# Balance.net
KiCad netlist of a schematic drawn in Altium Designer
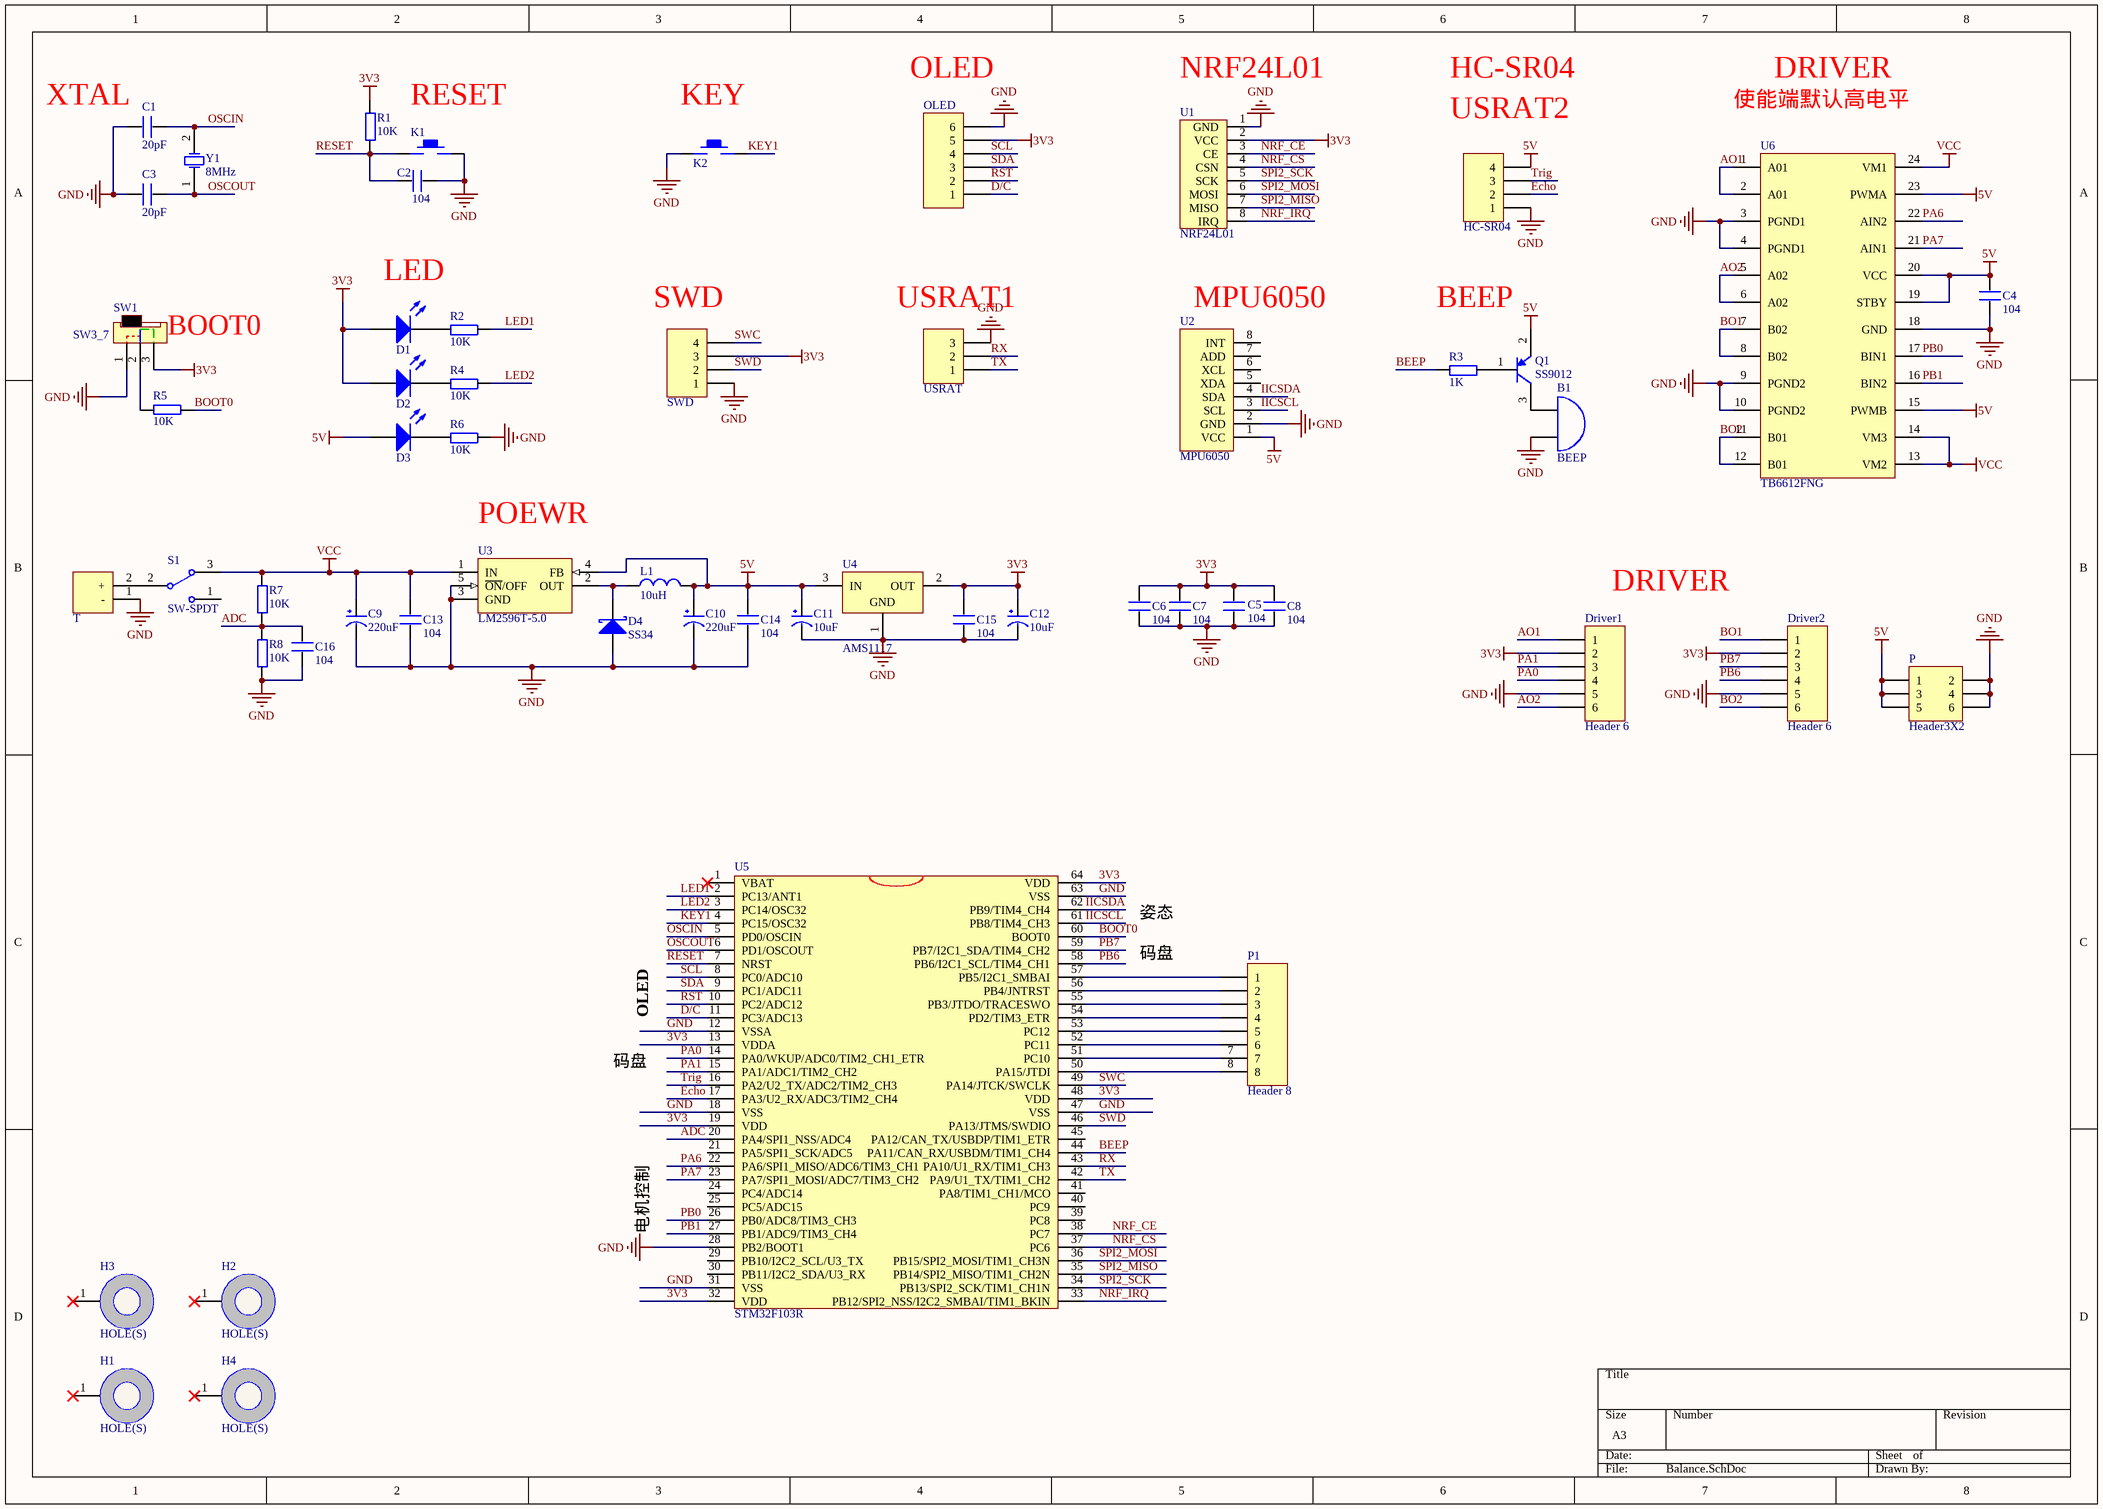
[diagram p0: Balance.SchDoc]

(export (version "E")
  (design (tool "Eeschema 10.0.6"))
  (components
    (comp (ref "B1")
      (value "BEEP")
      (footprint "STM32F103ZET6:BEEP")
      (description "蜂鸣器")
      (fields (field (name "PUBLISHER") "Altium Limited"))
      (libsource (lib "STM32F103ZET6") (part "BEEP"))
    )
    (comp (ref "C1")
      (value "20pF")
      (footprint "C-RAD-0805")
      (description "无极性电容")
      (libsource (lib "STM32F103ZET6") (part "C"))
    )
    (comp (ref "C2")
      (value "104")
      (footprint "C-RAD-0805")
      (description "无极性电容")
      (libsource (lib "STM32F103ZET6") (part "C"))
    )
    (comp (ref "C3")
      (value "20pF")
      (footprint "C-RAD-0805")
      (description "无极性电容")
      (libsource (lib "STM32F103ZET6") (part "C"))
    )
    (comp (ref "C4")
      (value "104")
      (footprint "C-RAD-0805")
      (description "无极性电容")
      (libsource (lib "STM32F103ZET6") (part "C"))
    )
    (comp (ref "C5")
      (value "104")
      (footprint "C-RAD-0805")
      (description "无极性电容")
      (libsource (lib "STM32F103ZET6") (part "C"))
    )
    (comp (ref "C6")
      (value "104")
      (footprint "C-RAD-0805")
      (description "无极性电容")
      (libsource (lib "STM32F103ZET6") (part "C"))
    )
    (comp (ref "C7")
      (value "104")
      (footprint "C-RAD-0805")
      (description "无极性电容")
      (libsource (lib "STM32F103ZET6") (part "C"))
    )
    (comp (ref "C8")
      (value "104")
      (footprint "C-RAD-0805")
      (description "无极性电容")
      (libsource (lib "STM32F103ZET6") (part "C"))
    )
    (comp (ref "C9")
      (value "220uF")
      (footprint "C-RB-8")
      (description "极性电容")
      (libsource (lib "STM32F103ZET6") (part "CAP"))
    )
    (comp (ref "C10")
      (value "220uF")
      (footprint "C-RB-8")
      (description "极性电容")
      (libsource (lib "STM32F103ZET6") (part "CAP"))
    )
    (comp (ref "C11")
      (value "10uF")
      (footprint "STM32F103ZET6:CAP-1206")
      (description "极性电容")
      (libsource (lib "STM32F103ZET6") (part "CAP"))
    )
    (comp (ref "C12")
      (value "10uF")
      (footprint "STM32F103ZET6:CAP-1206")
      (description "极性电容")
      (libsource (lib "STM32F103ZET6") (part "CAP"))
    )
    (comp (ref "C13")
      (value "104")
      (footprint "C-RAD-0805")
      (description "无极性电容")
      (libsource (lib "STM32F103ZET6") (part "C"))
    )
    (comp (ref "C14")
      (value "104")
      (footprint "C-RAD-0805")
      (description "无极性电容")
      (libsource (lib "STM32F103ZET6") (part "C"))
    )
    (comp (ref "C15")
      (value "104")
      (footprint "C-RAD-0805")
      (description "无极性电容")
      (libsource (lib "STM32F103ZET6") (part "C"))
    )
    (comp (ref "C16")
      (value "104")
      (footprint "C-RAD-0805")
      (description "无极性电容")
      (libsource (lib "STM32F103ZET6") (part "C"))
    )
    (comp (ref "D1")
      (value "LED")
      (footprint "STM32F103ZET6:SMDLED")
      (description "发光二极管")
      (fields (field (name "PUBLISHER") "Altium Limited"))
      (libsource (lib "STM32F103ZET6") (part "LED"))
    )
    (comp (ref "D2")
      (value "LED")
      (footprint "STM32F103ZET6:SMDLED")
      (description "发光二极管")
      (fields (field (name "PUBLISHER") "Altium Limited"))
      (libsource (lib "STM32F103ZET6") (part "LED"))
    )
    (comp (ref "D3")
      (value "LED")
      (footprint "STM32F103ZET6:SMDLED")
      (description "发光二极管")
      (fields (field (name "PUBLISHER") "Altium Limited"))
      (libsource (lib "STM32F103ZET6") (part "LED"))
    )
    (comp (ref "D4")
      (value "D-Schottky")
      (footprint "SMA")
      (description "肖特基二极管")
      (fields (field (name "TYPE") "SS34") (field (name "PUBLISHER") "Altium Limited"))
      (libsource (lib "STM32F103ZET6") (part "D-Schottky"))
    )
    (comp (ref "Driver1")
      (value "Header 6")
      (footprint "XH-6P")
      (description "接插件")
      (fields (field (name "PUBLISHER") "Altium Limited"))
      (libsource (lib "STM32F103ZET6") (part "Header 6"))
    )
    (comp (ref "Driver2")
      (value "Header 6")
      (footprint "XH-6P")
      (description "接插件")
      (fields (field (name "PUBLISHER") "Altium Limited"))
      (libsource (lib "STM32F103ZET6") (part "Header 6"))
    )
    (comp (ref "H1") (value "HOLE(S)") (footprint "HOLE9") (libsource (lib "STM32F103ZET6") (part "HOLE(S)")))
    (comp (ref "H2") (value "HOLE(S)") (footprint "HOLE9") (libsource (lib "STM32F103ZET6") (part "HOLE(S)")))
    (comp (ref "H3") (value "HOLE(S)") (footprint "HOLE9") (libsource (lib "STM32F103ZET6") (part "HOLE(S)")))
    (comp (ref "H4") (value "HOLE(S)") (footprint "HOLE9") (libsource (lib "STM32F103ZET6") (part "HOLE(S)")))
    (comp (ref "HC-SR04")
      (value "Header 4")
      (footprint "SIP4X2.54MM")
      (description "接插件")
      (fields (field (name "PUBLISHER") "Altium Limited"))
      (libsource (lib "STM32F103ZET6") (part "Header 4"))
    )
    (comp (ref "K1")
      (value "KEY_M")
      (footprint "SW2P3X6X4.3(SMD)")
      (description "轻触按键")
      (libsource (lib "STM32F103ZET6") (part "KEY_M"))
    )
    (comp (ref "K2")
      (value "KEY_M")
      (footprint "SW2P3X6X4.3(SMD)")
      (description "轻触按键")
      (libsource (lib "STM32F103ZET6") (part "KEY_M"))
    )
    (comp (ref "L1")
      (value "10uH")
      (footprint "L-SMD-10")
      (description "电感")
      (fields (field (name "Comment") "L") (field (name "PUBLISHER") "Altium Limited"))
      (libsource (lib "STM32F103ZET6") (part "L"))
    )
    (comp (ref "OLED")
      (value "~")
      (footprint "SIP6X2.54MM")
      (description "接插件")
      (fields (field (name "PUBLISHER") "Altium Limited"))
      (libsource (lib "") (part "Header 6_1"))
    )
    (comp (ref "P")
      (value "Header3X2")
      (footprint "STM32F103ZET6:HDR3X2")
      (description "接插件")
      (fields (field (name "PUBLISHER") "Altium Limited"))
      (libsource (lib "STM32F103ZET6") (part "Header3X2"))
    )
    (comp (ref "P1")
      (value "Header 8")
      (footprint "SIP8X2.54MM")
      (description "接插件")
      (fields (field (name "PUBLISHER") "Altium Limited"))
      (libsource (lib "STM32F103ZET6") (part "Header 8"))
    )
    (comp (ref "Q1")
      (value "SS9012")
      (footprint "SOT-23")
      (description "PNP贴片三极管")
      (fields (field (name "PUBLISHER") "Altium Limited"))
      (libsource (lib "STM32F103ZET6") (part "SS8550"))
    )
    (comp (ref "R1") (value "10K") (footprint "0805") (libsource (lib "STM32F103ZET6") (part "R")))
    (comp (ref "R2") (value "10K") (footprint "0805") (libsource (lib "STM32F103ZET6") (part "R")))
    (comp (ref "R3") (value "1K") (footprint "0805") (libsource (lib "STM32F103ZET6") (part "R")))
    (comp (ref "R4") (value "10K") (footprint "0805") (libsource (lib "STM32F103ZET6") (part "R")))
    (comp (ref "R5") (value "10K") (footprint "0805") (libsource (lib "STM32F103ZET6") (part "R")))
    (comp (ref "R6") (value "10K") (footprint "0805") (libsource (lib "STM32F103ZET6") (part "R")))
    (comp (ref "R7") (value "10K") (footprint "0805") (libsource (lib "STM32F103ZET6") (part "R")))
    (comp (ref "R8") (value "10K") (footprint "0805") (libsource (lib "STM32F103ZET6") (part "R")))
    (comp (ref "S1")
      (value "SW-SPDT")
      (footprint "switch")
      (description "开关")
      (fields (field (name "PUBLISHER") "Altium Limited"))
      (libsource (lib "STM32F103ZET6") (part "SW-SPDT"))
    )
    (comp (ref "SW1")
      (value "SW3_7")
      (footprint "MSK-02-7")
      (description "3脚2档侧面拨动 7Pin微动开关")
      (libsource (lib "STM32F103ZET6") (part "SW3_7"))
    )
    (comp (ref "SWD")
      (value "Header 4")
      (footprint "XH-4P")
      (description "接插件")
      (fields (field (name "PUBLISHER") "Altium Limited"))
      (libsource (lib "STM32F103ZET6") (part "Header 4"))
    )
    (comp (ref "T")
      (value "TCON")
      (footprint "Tcon")
      (description "T插")
      (fields (field (name "PUBLISHER") "Altium Limited"))
      (libsource (lib "STM32F103ZET6") (part "TCON"))
    )
    (comp (ref "U1")
      (value "NRF24L01")
      (footprint "STM32F103ZET6:NRF24L01")
      (description "无线模块")
      (libsource (lib "STM32F103ZET6") (part "NRF24L01"))
    )
    (comp (ref "U2")
      (value "MPU6050")
      (footprint "SIP8X2.54MM")
      (fields (field (name "PUBLISHER") "Altium Limited"))
      (libsource (lib "STM32F103ZET6") (part "MPU6050"))
    )
    (comp (ref "U3")
      (value "LM2596T-5.0")
      (footprint "TO-263-5")
      (description "5V稳压芯片")
      (fields (field (name "PUBLISHER") "Altium Limited"))
      (libsource (lib "STM32F103ZET6") (part "LM2596T-5.0"))
    )
    (comp (ref "U4")
      (value "AMS1117")
      (footprint "AMS-1117")
      (description "3.3V稳压")
      (libsource (lib "STM32F103ZET6") (part "AMS1117"))
    )
    (comp (ref "U5")
      (value "STM32F103R")
      (footprint "LQFP-64")
      (description "STM32单片机48引脚")
      (libsource (lib "STM32F103ZET6") (part "STM32F103R"))
    )
    (comp (ref "U6")
      (value "TB6612FNG")
      (footprint "SSOP-24")
      (description "电机驱动")
      (libsource (lib "STM32F103ZET6") (part "TB6612FNG"))
    )
    (comp (ref "USRAT")
      (value "Header 3")
      (footprint "XH-3P")
      (description "接插件")
      (fields (field (name "PUBLISHER") "Altium Limited"))
      (libsource (lib "STM32F103ZET6") (part "Header 3"))
    )
    (comp (ref "Y1")
      (value "8MHz")
      (footprint "XTAL")
      (description "Crystal Oscillator")
      (fields (field (name "PUBLISHER") "Altium Limited"))
      (libsource (lib "STM32F103ZET6") (part "XTAL"))
    )
  )
  (nets
    (net (code "1") (name "/ADC") (class "Default")
      (node (ref "C16") (pin "2") (pintype "passive"))
      (node (ref "R7") (pin "1") (pintype "passive"))
      (node (ref "R8") (pin "2") (pintype "passive"))
      (node (ref "U5") (pin "20") (pinfunction "PA4/SPI1_NSS/ADC4_20") (pintype "passive"))
    )
    (net (code "2") (name "/AO1") (class "Default")
      (node (ref "Driver1") (pin "1") (pinfunction "1_1") (pintype "passive"))
      (node (ref "U6") (pin "1") (pinfunction "A01_1") (pintype "passive"))
      (node (ref "U6") (pin "2") (pinfunction "A01_2") (pintype "passive"))
    )
    (net (code "3") (name "/AO2") (class "Default")
      (node (ref "Driver1") (pin "6") (pinfunction "6_6") (pintype "passive"))
      (node (ref "U6") (pin "5") (pinfunction "A02_5") (pintype "passive"))
      (node (ref "U6") (pin "6") (pinfunction "A02_6") (pintype "passive"))
    )
    (net (code "4") (name "/BEEP") (class "Default")
      (node (ref "R3") (pin "1") (pintype "passive"))
      (node (ref "U5") (pin "44") (pinfunction "PA11/CAN_RX/USBDM/TIM1_CH4_44") (pintype "passive"))
    )
    (net (code "5") (name "/BO1") (class "Default")
      (node (ref "Driver2") (pin "1") (pinfunction "1_1") (pintype "passive"))
      (node (ref "U6") (pin "7") (pinfunction "B02_7") (pintype "passive"))
      (node (ref "U6") (pin "8") (pinfunction "B02_8") (pintype "passive"))
    )
    (net (code "6") (name "/BO2") (class "Default")
      (node (ref "Driver2") (pin "6") (pinfunction "6_6") (pintype "passive"))
      (node (ref "U6") (pin "11") (pinfunction "B01_11") (pintype "passive"))
      (node (ref "U6") (pin "12") (pinfunction "B01_12") (pintype "passive"))
    )
    (net (code "7") (name "/BOOT0") (class "Default")
      (node (ref "R5") (pin "1") (pintype "passive"))
      (node (ref "U5") (pin "60") (pinfunction "BOOT0_60") (pintype "passive"))
    )
    (net (code "8") (name "/D{slash}C") (class "Default")
      (node (ref "OLED") (pin "1") (pinfunction "1_1") (pintype "passive"))
      (node (ref "U5") (pin "11") (pinfunction "PC3/ADC13_11") (pintype "passive"))
    )
    (net (code "9") (name "/Echo") (class "Default")
      (node (ref "HC-SR04") (pin "2") (pinfunction "2_2") (pintype "passive"))
      (node (ref "U5") (pin "17") (pinfunction "PA3/U2_RX/ADC3/TIM2_CH4_17") (pintype "passive"))
    )
    (net (code "10") (name "/IICSCL") (class "Default")
      (node (ref "U2") (pin "3") (pinfunction "SCL_3") (pintype "passive"))
      (node (ref "U5") (pin "61") (pinfunction "PB8/TIM4_CH3_61") (pintype "passive"))
    )
    (net (code "11") (name "/IICSDA") (class "Default")
      (node (ref "U2") (pin "4") (pinfunction "SDA_4") (pintype "passive"))
      (node (ref "U5") (pin "62") (pinfunction "PB9/TIM4_CH4_62") (pintype "passive"))
    )
    (net (code "12") (name "/KEY1") (class "Default")
      (node (ref "K2") (pin "2") (pinfunction "2_2") (pintype "passive"))
      (node (ref "U5") (pin "4") (pinfunction "PC15/OSC32_4") (pintype "passive"))
    )
    (net (code "13") (name "/LED1") (class "Default")
      (node (ref "R2") (pin "2") (pintype "passive"))
      (node (ref "U5") (pin "2") (pinfunction "PC13/ANT1_2") (pintype "passive"))
    )
    (net (code "14") (name "/LED2") (class "Default")
      (node (ref "R4") (pin "2") (pintype "passive"))
      (node (ref "U5") (pin "3") (pinfunction "PC14/OSC32_3") (pintype "passive"))
    )
    (net (code "15") (name "/NRF_CE") (class "Default")
      (node (ref "U1") (pin "3") (pinfunction "CE_3") (pintype "passive"))
      (node (ref "U5") (pin "38") (pinfunction "PC7_38") (pintype "passive"))
    )
    (net (code "16") (name "/NRF_CS") (class "Default")
      (node (ref "U1") (pin "4") (pinfunction "CSN_4") (pintype "passive"))
      (node (ref "U5") (pin "37") (pinfunction "PC6_37") (pintype "passive"))
    )
    (net (code "17") (name "/NRF_IRQ") (class "Default")
      (node (ref "U1") (pin "8") (pinfunction "IRQ_8") (pintype "passive"))
      (node (ref "U5") (pin "33") (pinfunction "PB12/SPI2_NSS/I2C2_SMBAI/TIM1_BKIN_33") (pintype "passive"))
    )
    (net (code "18") (name "/OSCIN") (class "Default")
      (node (ref "C1") (pin "2") (pintype "passive"))
      (node (ref "U5") (pin "5") (pinfunction "PD0/OSCIN_5") (pintype "passive"))
      (node (ref "Y1") (pin "2") (pinfunction "OSC2_2") (pintype "passive"))
    )
    (net (code "19") (name "/OSCOUT") (class "Default")
      (node (ref "C3") (pin "2") (pintype "passive"))
      (node (ref "U5") (pin "6") (pinfunction "PD1/OSCOUT_6") (pintype "passive"))
      (node (ref "Y1") (pin "1") (pinfunction "OSC1_1") (pintype "passive"))
    )
    (net (code "20") (name "/PA0") (class "Default")
      (node (ref "Driver1") (pin "4") (pinfunction "4_4") (pintype "passive"))
      (node (ref "U5") (pin "14") (pinfunction "PA0/WKUP/ADC0/TIM2_CH1_ETR_14") (pintype "passive"))
    )
    (net (code "21") (name "/PA1") (class "Default")
      (node (ref "Driver1") (pin "3") (pinfunction "3_3") (pintype "passive"))
      (node (ref "U5") (pin "15") (pinfunction "PA1/ADC1/TIM2_CH2_15") (pintype "passive"))
    )
    (net (code "22") (name "/PA6") (class "Default")
      (node (ref "U5") (pin "22") (pinfunction "PA6/SPI1_MISO/ADC6/TIM3_CH1_22") (pintype "passive"))
      (node (ref "U6") (pin "22") (pinfunction "AIN2_22") (pintype "passive"))
    )
    (net (code "23") (name "/PA7") (class "Default")
      (node (ref "U5") (pin "23") (pinfunction "PA7/SPI1_MOSI/ADC7/TIM3_CH2_23") (pintype "passive"))
      (node (ref "U6") (pin "21") (pinfunction "AIN1_21") (pintype "passive"))
    )
    (net (code "24") (name "/PB0") (class "Default")
      (node (ref "U5") (pin "26") (pinfunction "PB0/ADC8/TIM3_CH3_26") (pintype "passive"))
      (node (ref "U6") (pin "17") (pinfunction "BIN1_17") (pintype "passive"))
    )
    (net (code "25") (name "/PB1") (class "Default")
      (node (ref "U5") (pin "27") (pinfunction "PB1/ADC9/TIM3_CH4_27") (pintype "passive"))
      (node (ref "U6") (pin "16") (pinfunction "BIN2_16") (pintype "passive"))
    )
    (net (code "26") (name "/PB6") (class "Default")
      (node (ref "Driver2") (pin "4") (pinfunction "4_4") (pintype "passive"))
      (node (ref "U5") (pin "58") (pinfunction "PB6/I2C1_SCL/TIM4_CH1_58") (pintype "passive"))
    )
    (net (code "27") (name "/PB7") (class "Default")
      (node (ref "Driver2") (pin "3") (pinfunction "3_3") (pintype "passive"))
      (node (ref "U5") (pin "59") (pinfunction "PB7/I2C1_SDA/TIM4_CH2_59") (pintype "passive"))
    )
    (net (code "28") (name "/RESET") (class "Default")
      (node (ref "C2") (pin "2") (pintype "passive"))
      (node (ref "K1") (pin "1") (pinfunction "1_1") (pintype "passive"))
      (node (ref "R1") (pin "1") (pintype "passive"))
      (node (ref "U5") (pin "7") (pinfunction "NRST_7") (pintype "passive"))
    )
    (net (code "29") (name "/RST") (class "Default")
      (node (ref "OLED") (pin "2") (pinfunction "2_2") (pintype "passive"))
      (node (ref "U5") (pin "10") (pinfunction "PC2/ADC12_10") (pintype "passive"))
    )
    (net (code "30") (name "/RX") (class "Default")
      (node (ref "U5") (pin "43") (pinfunction "PA10/U1_RX/TIM1_CH3_43") (pintype "passive"))
      (node (ref "USRAT") (pin "2") (pinfunction "2_2") (pintype "passive"))
    )
    (net (code "31") (name "/SCL") (class "Default")
      (node (ref "OLED") (pin "4") (pinfunction "4_4") (pintype "passive"))
      (node (ref "U5") (pin "8") (pinfunction "PC0/ADC10_8") (pintype "passive"))
    )
    (net (code "32") (name "/SDA") (class "Default")
      (node (ref "OLED") (pin "3") (pinfunction "3_3") (pintype "passive"))
      (node (ref "U5") (pin "9") (pinfunction "PC1/ADC11_9") (pintype "passive"))
    )
    (net (code "33") (name "/SPI2_MISO") (class "Default")
      (node (ref "U1") (pin "7") (pinfunction "MISO_7") (pintype "passive"))
      (node (ref "U5") (pin "35") (pinfunction "PB14/SPI2_MISO/TIM1_CH2N_35") (pintype "passive"))
    )
    (net (code "34") (name "/SPI2_MOSI") (class "Default")
      (node (ref "U1") (pin "6") (pinfunction "MOSI_6") (pintype "passive"))
      (node (ref "U5") (pin "36") (pinfunction "PB15/SPI2_MOSI/TIM1_CH3N_36") (pintype "passive"))
    )
    (net (code "35") (name "/SPI2_SCK") (class "Default")
      (node (ref "U1") (pin "5") (pinfunction "SCK_5") (pintype "passive"))
      (node (ref "U5") (pin "34") (pinfunction "PB13/SPI2_SCK/TIM1_CH1N_34") (pintype "passive"))
    )
    (net (code "36") (name "/SWC") (class "Default")
      (node (ref "SWD") (pin "4") (pinfunction "4_4") (pintype "passive"))
      (node (ref "U5") (pin "49") (pinfunction "PA14/JTCK/SWCLK_49") (pintype "passive"))
    )
    (net (code "37") (name "/SWD") (class "Default")
      (node (ref "SWD") (pin "2") (pinfunction "2_2") (pintype "passive"))
      (node (ref "U5") (pin "46") (pinfunction "PA13/JTMS/SWDIO_46") (pintype "passive"))
    )
    (net (code "38") (name "/TX") (class "Default")
      (node (ref "U5") (pin "42") (pinfunction "PA9/U1_TX/TIM1_CH2_42") (pintype "passive"))
      (node (ref "USRAT") (pin "1") (pinfunction "1_1") (pintype "passive"))
    )
    (net (code "39") (name "/Trig") (class "Default")
      (node (ref "HC-SR04") (pin "3") (pinfunction "3_3") (pintype "passive"))
      (node (ref "U5") (pin "16") (pinfunction "PA2/U2_TX/ADC2/TIM2_CH3_16") (pintype "passive"))
    )
    (net (code "40") (name "3V3") (class "Default")
      (node (ref "C12") (pin "1") (pinfunction "VCC_1") (pintype "passive"))
      (node (ref "C15") (pin "2") (pintype "passive"))
      (node (ref "C5") (pin "2") (pintype "passive"))
      (node (ref "C6") (pin "2") (pintype "passive"))
      (node (ref "C7") (pin "2") (pintype "passive"))
      (node (ref "C8") (pin "2") (pintype "passive"))
      (node (ref "D1") (pin "1") (pinfunction "A_1") (pintype "passive"))
      (node (ref "D2") (pin "1") (pinfunction "A_1") (pintype "passive"))
      (node (ref "Driver1") (pin "2") (pinfunction "2_2") (pintype "passive"))
      (node (ref "Driver2") (pin "2") (pinfunction "2_2") (pintype "passive"))
      (node (ref "OLED") (pin "5") (pinfunction "5_5") (pintype "passive"))
      (node (ref "R1") (pin "2") (pintype "passive"))
      (node (ref "SW1") (pin "3") (pinfunction "3_3") (pintype "power_in"))
      (node (ref "SWD") (pin "3") (pinfunction "3_3") (pintype "passive"))
      (node (ref "U1") (pin "2") (pinfunction "VCC_2") (pintype "passive"))
      (node (ref "U4") (pin "2") (pinfunction "OUT_2") (pintype "power_in"))
      (node (ref "U5") (pin "13") (pinfunction "VDDA_13") (pintype "passive"))
      (node (ref "U5") (pin "19") (pinfunction "VDD_19") (pintype "passive"))
      (node (ref "U5") (pin "32") (pinfunction "VDD_32") (pintype "passive"))
      (node (ref "U5") (pin "48") (pinfunction "VDD_48") (pintype "passive"))
      (node (ref "U5") (pin "64") (pinfunction "VDD_64") (pintype "passive"))
    )
    (net (code "41") (name "5V") (class "Default")
      (node (ref "C10") (pin "1") (pinfunction "VCC_1") (pintype "passive"))
      (node (ref "C11") (pin "1") (pinfunction "VCC_1") (pintype "passive"))
      (node (ref "C14") (pin "2") (pintype "passive"))
      (node (ref "C4") (pin "2") (pintype "passive"))
      (node (ref "D3") (pin "1") (pinfunction "A_1") (pintype "passive"))
      (node (ref "HC-SR04") (pin "4") (pinfunction "4_4") (pintype "passive"))
      (node (ref "L1") (pin "2") (pinfunction "2_2") (pintype "passive"))
      (node (ref "P") (pin "1") (pinfunction "1_1") (pintype "passive"))
      (node (ref "P") (pin "3") (pinfunction "3_3") (pintype "passive"))
      (node (ref "P") (pin "5") (pinfunction "5_5") (pintype "passive"))
      (node (ref "Q1") (pin "2") (pinfunction "E_2") (pintype "passive"))
      (node (ref "U2") (pin "1") (pinfunction "VCC_1") (pintype "passive"))
      (node (ref "U3") (pin "4") (pinfunction "FB_4") (pintype "input"))
      (node (ref "U4") (pin "3") (pinfunction "IN_3") (pintype "power_in"))
      (node (ref "U6") (pin "15") (pinfunction "PWMB_15") (pintype "passive"))
      (node (ref "U6") (pin "19") (pinfunction "STBY_19") (pintype "passive"))
      (node (ref "U6") (pin "20") (pinfunction "VCC_20") (pintype "passive"))
      (node (ref "U6") (pin "23") (pinfunction "PWMA_23") (pintype "passive"))
    )
    (net (code "42") (name "GND") (class "Default")
      (node (ref "B1") (pin "2") (pinfunction "B_2") (pintype "passive"))
      (node (ref "C1") (pin "1") (pintype "passive"))
      (node (ref "C10") (pin "2") (pinfunction "GND_2") (pintype "passive"))
      (node (ref "C11") (pin "2") (pinfunction "GND_2") (pintype "passive"))
      (node (ref "C12") (pin "2") (pinfunction "GND_2") (pintype "passive"))
      (node (ref "C13") (pin "1") (pintype "passive"))
      (node (ref "C14") (pin "1") (pintype "passive"))
      (node (ref "C15") (pin "1") (pintype "passive"))
      (node (ref "C16") (pin "1") (pintype "passive"))
      (node (ref "C2") (pin "1") (pintype "passive"))
      (node (ref "C3") (pin "1") (pintype "passive"))
      (node (ref "C4") (pin "1") (pintype "passive"))
      (node (ref "C5") (pin "1") (pintype "passive"))
      (node (ref "C6") (pin "1") (pintype "passive"))
      (node (ref "C7") (pin "1") (pintype "passive"))
      (node (ref "C8") (pin "1") (pintype "passive"))
      (node (ref "C9") (pin "2") (pinfunction "GND_2") (pintype "passive"))
      (node (ref "D4") (pin "1") (pinfunction "A_1") (pintype "passive"))
      (node (ref "Driver1") (pin "5") (pinfunction "5_5") (pintype "passive"))
      (node (ref "Driver2") (pin "5") (pinfunction "5_5") (pintype "passive"))
      (node (ref "HC-SR04") (pin "1") (pinfunction "1_1") (pintype "passive"))
      (node (ref "K1") (pin "2") (pinfunction "2_2") (pintype "passive"))
      (node (ref "K2") (pin "1") (pinfunction "1_1") (pintype "passive"))
      (node (ref "OLED") (pin "6") (pinfunction "6_6") (pintype "passive"))
      (node (ref "P") (pin "2") (pinfunction "2_2") (pintype "passive"))
      (node (ref "P") (pin "4") (pinfunction "4_4") (pintype "passive"))
      (node (ref "P") (pin "6") (pinfunction "6_6") (pintype "passive"))
      (node (ref "R6") (pin "2") (pintype "passive"))
      (node (ref "R8") (pin "1") (pintype "passive"))
      (node (ref "SW1") (pin "1") (pinfunction "1_1") (pintype "power_in"))
      (node (ref "SWD") (pin "1") (pinfunction "1_1") (pintype "passive"))
      (node (ref "T") (pin "1") (pinfunction "-_1") (pintype "passive"))
      (node (ref "U1") (pin "1") (pinfunction "GND_1") (pintype "passive"))
      (node (ref "U2") (pin "2") (pinfunction "GND_2") (pintype "passive"))
      (node (ref "U3") (pin "3") (pinfunction "GND_3") (pintype "power_in"))
      (node (ref "U3") (pin "5") (pinfunction "~{ON}/OFF_5") (pintype "input"))
      (node (ref "U4") (pin "1") (pinfunction "GND_1") (pintype "power_in"))
      (node (ref "U5") (pin "12") (pinfunction "VSSA_12") (pintype "passive"))
      (node (ref "U5") (pin "18") (pinfunction "VSS_18") (pintype "passive"))
      (node (ref "U5") (pin "28") (pinfunction "PB2/BOOT1_28") (pintype "passive"))
      (node (ref "U5") (pin "31") (pinfunction "VSS_31") (pintype "passive"))
      (node (ref "U5") (pin "47") (pinfunction "VSS_47") (pintype "passive"))
      (node (ref "U5") (pin "63") (pinfunction "VSS_63") (pintype "passive"))
      (node (ref "U6") (pin "10") (pinfunction "PGND2_10") (pintype "passive"))
      (node (ref "U6") (pin "18") (pinfunction "GND_18") (pintype "passive"))
      (node (ref "U6") (pin "3") (pinfunction "PGND1_3") (pintype "passive"))
      (node (ref "U6") (pin "4") (pinfunction "PGND1_4") (pintype "passive"))
      (node (ref "U6") (pin "9") (pinfunction "PGND2_9") (pintype "passive"))
      (node (ref "USRAT") (pin "3") (pinfunction "3_3") (pintype "passive"))
    )
    (net (code "43") (name "Net-(B1-A)") (class "Default")
      (node (ref "B1") (pin "1") (pinfunction "A_1") (pintype "passive"))
      (node (ref "Q1") (pin "3") (pinfunction "C_3") (pintype "passive"))
    )
    (net (code "44") (name "Net-(D1-K)") (class "Default")
      (node (ref "D1") (pin "2") (pinfunction "K_2") (pintype "passive"))
      (node (ref "R2") (pin "1") (pintype "passive"))
    )
    (net (code "45") (name "Net-(D2-K)") (class "Default")
      (node (ref "D2") (pin "2") (pinfunction "K_2") (pintype "passive"))
      (node (ref "R4") (pin "1") (pintype "passive"))
    )
    (net (code "46") (name "Net-(D3-K)") (class "Default")
      (node (ref "D3") (pin "2") (pinfunction "K_2") (pintype "passive"))
      (node (ref "R6") (pin "1") (pintype "passive"))
    )
    (net (code "47") (name "Net-(D4-K)") (class "Default")
      (node (ref "D4") (pin "2") (pinfunction "K_2") (pintype "passive"))
      (node (ref "L1") (pin "1") (pinfunction "1_1") (pintype "passive"))
      (node (ref "U3") (pin "2") (pinfunction "OUT_2") (pintype "power_in"))
    )
    (net (code "48") (name "Net-(Q1-B)") (class "Default")
      (node (ref "Q1") (pin "1") (pinfunction "B_1") (pintype "passive"))
      (node (ref "R3") (pin "2") (pintype "passive"))
    )
    (net (code "49") (name "Net-(R5-Pad2)") (class "Default")
      (node (ref "R5") (pin "2") (pintype "passive"))
      (node (ref "SW1") (pin "2") (pinfunction "2_2") (pintype "power_in"))
    )
    (net (code "50") (name "Net-(T-+)") (class "Default")
      (node (ref "S1") (pin "2") (pinfunction "2_2") (pintype "passive"))
      (node (ref "T") (pin "2") (pinfunction "+_2") (pintype "passive"))
    )
    (net (code "51") (name "Net-(U5-PA15{slash}JTDI)") (class "Default")
      (node (ref "P1") (pin "8") (pinfunction "8_8") (pintype "passive"))
      (node (ref "U5") (pin "50") (pinfunction "PA15/JTDI_50") (pintype "passive"))
    )
    (net (code "52") (name "Net-(U5-PB3{slash}JTDO{slash}TRACESWO)") (class "Default")
      (node (ref "P1") (pin "3") (pinfunction "3_3") (pintype "passive"))
      (node (ref "U5") (pin "55") (pinfunction "PB3/JTDO/TRACESWO_55") (pintype "passive"))
    )
    (net (code "53") (name "Net-(U5-PB4{slash}JNTRST)") (class "Default")
      (node (ref "P1") (pin "2") (pinfunction "2_2") (pintype "passive"))
      (node (ref "U5") (pin "56") (pinfunction "PB4/JNTRST_56") (pintype "passive"))
    )
    (net (code "54") (name "Net-(U5-PB5{slash}I2C1_SMBAI)") (class "Default")
      (node (ref "P1") (pin "1") (pinfunction "1_1") (pintype "passive"))
      (node (ref "U5") (pin "57") (pinfunction "PB5/I2C1_SMBAI_57") (pintype "passive"))
    )
    (net (code "55") (name "Net-(U5-PC10)") (class "Default")
      (node (ref "P1") (pin "7") (pinfunction "7_7") (pintype "passive"))
      (node (ref "U5") (pin "51") (pinfunction "PC10_51") (pintype "passive"))
    )
    (net (code "56") (name "Net-(U5-PC11)") (class "Default")
      (node (ref "P1") (pin "6") (pinfunction "6_6") (pintype "passive"))
      (node (ref "U5") (pin "52") (pinfunction "PC11_52") (pintype "passive"))
    )
    (net (code "57") (name "Net-(U5-PC12)") (class "Default")
      (node (ref "P1") (pin "5") (pinfunction "5_5") (pintype "passive"))
      (node (ref "U5") (pin "53") (pinfunction "PC12_53") (pintype "passive"))
    )
    (net (code "58") (name "Net-(U5-PD2{slash}TIM3_ETR)") (class "Default")
      (node (ref "P1") (pin "4") (pinfunction "4_4") (pintype "passive"))
      (node (ref "U5") (pin "54") (pinfunction "PD2/TIM3_ETR_54") (pintype "passive"))
    )
    (net (code "59") (name "VCC") (class "Default")
      (node (ref "C13") (pin "2") (pintype "passive"))
      (node (ref "C9") (pin "1") (pinfunction "VCC_1") (pintype "passive"))
      (node (ref "R7") (pin "2") (pintype "passive"))
      (node (ref "S1") (pin "3") (pinfunction "3_3") (pintype "passive"))
      (node (ref "U3") (pin "1") (pinfunction "IN_1") (pintype "power_in"))
      (node (ref "U6") (pin "13") (pinfunction "VM2_13") (pintype "passive"))
      (node (ref "U6") (pin "14") (pinfunction "VM3_14") (pintype "passive"))
      (node (ref "U6") (pin "24") (pinfunction "VM1_24") (pintype "passive"))
    )
    (net (code "60") (name "unconnected-(H1-HOLE-Pad1)") (class "Default")
      (node (ref "H1") (pin "1") (pinfunction "HOLE_1") (pintype "passive+no_connect"))
    )
    (net (code "61") (name "unconnected-(H2-HOLE-Pad1)") (class "Default")
      (node (ref "H2") (pin "1") (pinfunction "HOLE_1") (pintype "passive+no_connect"))
    )
    (net (code "62") (name "unconnected-(H3-HOLE-Pad1)") (class "Default")
      (node (ref "H3") (pin "1") (pinfunction "HOLE_1") (pintype "passive+no_connect"))
    )
    (net (code "63") (name "unconnected-(H4-HOLE-Pad1)") (class "Default")
      (node (ref "H4") (pin "1") (pinfunction "HOLE_1") (pintype "passive+no_connect"))
    )
    (net (code "64") (name "unconnected-(S1-Pad1)") (class "Default")
      (node (ref "S1") (pin "1") (pinfunction "1_1") (pintype "passive"))
    )
    (net (code "65") (name "unconnected-(U2-ADD-Pad7)") (class "Default")
      (node (ref "U2") (pin "7") (pinfunction "ADD_7") (pintype "passive"))
    )
    (net (code "66") (name "unconnected-(U2-INT-Pad8)") (class "Default")
      (node (ref "U2") (pin "8") (pinfunction "INT_8") (pintype "passive"))
    )
    (net (code "67") (name "unconnected-(U2-XCL-Pad6)") (class "Default")
      (node (ref "U2") (pin "6") (pinfunction "XCL_6") (pintype "passive"))
    )
    (net (code "68") (name "unconnected-(U2-XDA-Pad5)") (class "Default")
      (node (ref "U2") (pin "5") (pinfunction "XDA_5") (pintype "passive"))
    )
    (net (code "69") (name "unconnected-(U5-PA5{slash}SPI1_SCK{slash}ADC5-Pad21)") (class "Default")
      (node (ref "U5") (pin "21") (pinfunction "PA5/SPI1_SCK/ADC5_21") (pintype "passive"))
    )
    (net (code "70") (name "unconnected-(U5-PA8{slash}TIM1_CH1{slash}MCO-Pad41)") (class "Default")
      (node (ref "U5") (pin "41") (pinfunction "PA8/TIM1_CH1/MCO_41") (pintype "passive"))
    )
    (net (code "71") (name "unconnected-(U5-PA12{slash}CAN_TX{slash}USBDP{slash}TIM1_ETR-Pad45)") (class "Default")
      (node (ref "U5") (pin "45") (pinfunction "PA12/CAN_TX/USBDP/TIM1_ETR_45") (pintype "passive"))
    )
    (net (code "72") (name "unconnected-(U5-PB10{slash}I2C2_SCL{slash}U3_TX-Pad29)") (class "Default")
      (node (ref "U5") (pin "29") (pinfunction "PB10/I2C2_SCL/U3_TX_29") (pintype "passive"))
    )
    (net (code "73") (name "unconnected-(U5-PB11{slash}I2C2_SDA{slash}U3_RX-Pad30)") (class "Default")
      (node (ref "U5") (pin "30") (pinfunction "PB11/I2C2_SDA/U3_RX_30") (pintype "passive"))
    )
    (net (code "74") (name "unconnected-(U5-PC4{slash}ADC14-Pad24)") (class "Default")
      (node (ref "U5") (pin "24") (pinfunction "PC4/ADC14_24") (pintype "passive"))
    )
    (net (code "75") (name "unconnected-(U5-PC5{slash}ADC15-Pad25)") (class "Default")
      (node (ref "U5") (pin "25") (pinfunction "PC5/ADC15_25") (pintype "passive"))
    )
    (net (code "76") (name "unconnected-(U5-PC8-Pad39)") (class "Default")
      (node (ref "U5") (pin "39") (pinfunction "PC8_39") (pintype "passive"))
    )
    (net (code "77") (name "unconnected-(U5-PC9-Pad40)") (class "Default")
      (node (ref "U5") (pin "40") (pinfunction "PC9_40") (pintype "passive"))
    )
    (net (code "78") (name "unconnected-(U5-VBAT-Pad1)") (class "Default")
      (node (ref "U5") (pin "1") (pinfunction "VBAT_1") (pintype "passive+no_connect"))
    )
  )
)
